# USB_to_Serial_Connector_A.net
KiCad netlist of a schematic drawn in Altium Designer
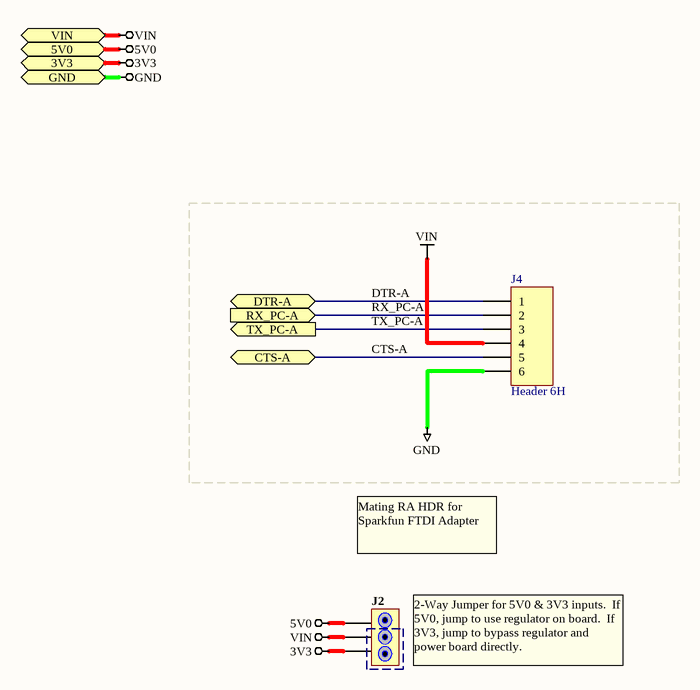
[diagram p0: USB to Serial Connector A.SchDoc]

(export (version "E")
  (design (tool "Eeschema 10.0.6"))
  (components
    (comp (ref "J2")
      (value "3-WAY JUMPER")
      (footprint "HDR1X3")
      (description "3-Way Jumper - Center Output")
      (libsource (lib "ESP Programming") (part "3-WAY JUMPER"))
    )
    (comp (ref "J4")
      (value "Header 6H")
      (footprint "HDR1X6H")
      (description "Header, 6-Pin, Right Angle")
      (fields (field (name "PUBLISHER") "Altium Limited"))
      (libsource (lib "Miscellaneous Connectors") (part "Header 6H"))
    )
  )
  (nets
    (net (code "1") (name "/CTS-A") (class "Default")
      (node (ref "J4") (pin "5") (pinfunction "5_5") (pintype "passive"))
    )
    (net (code "2") (name "/DTR-A") (class "Default")
      (node (ref "J4") (pin "1") (pinfunction "1_1") (pintype "passive"))
    )
    (net (code "3") (name "/RX_PC-A") (class "Default")
      (node (ref "J4") (pin "2") (pinfunction "2_2") (pintype "passive"))
    )
    (net (code "4") (name "/TX_PC-A") (class "Default")
      (node (ref "J4") (pin "3") (pinfunction "3_3") (pintype "passive"))
    )
    (net (code "5") (name "3V3") (class "Default")
      (node (ref "J2") (pin "1") (pinfunction "1_1") (pintype "passive"))
    )
    (net (code "6") (name "5V0") (class "Default")
      (node (ref "J2") (pin "3") (pinfunction "3_3") (pintype "passive"))
    )
    (net (code "7") (name "GND") (class "Default")
      (node (ref "J4") (pin "6") (pinfunction "6_6") (pintype "passive"))
    )
    (net (code "8") (name "VIN") (class "Default")
      (node (ref "J2") (pin "2") (pinfunction "2_2") (pintype "passive"))
      (node (ref "J4") (pin "4") (pinfunction "4_4") (pintype "passive"))
    )
  )
)
